# DebugProbe.net
KiCad netlist of a schematic drawn in Altium Designer
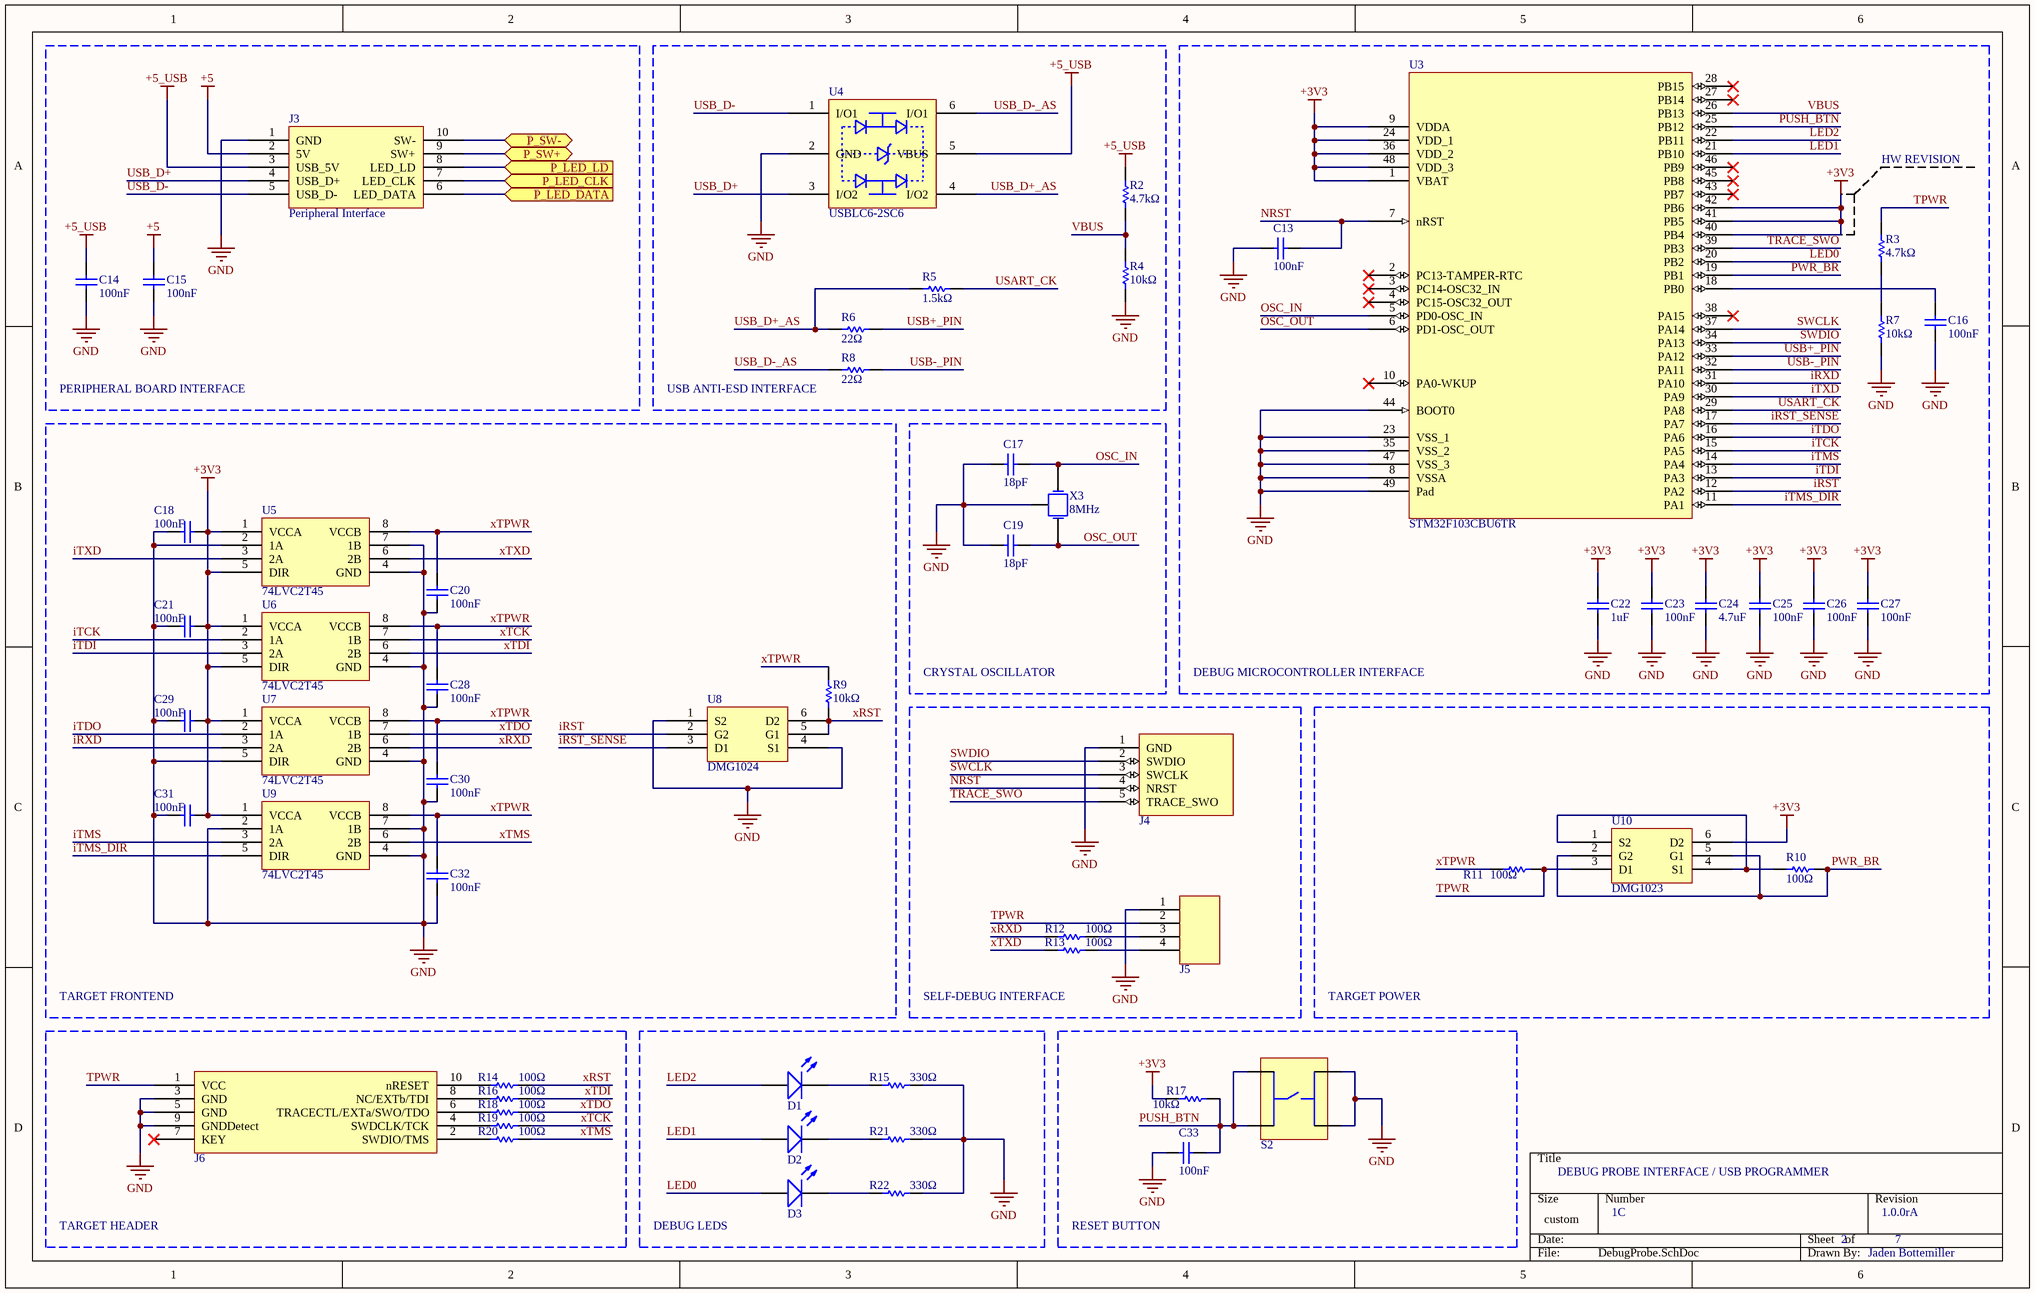
[diagram p0: DebugProbe.SchDoc]

(export (version "E")
  (design (tool "Eeschema 10.0.6"))
  (components
    (comp (ref "C13")
      (value "100nF")
      (description "Standard Capacitor")
      (fields (field (name "Comment") "CAP"))
      (libsource (lib "NikoboticsLib") (part "CAP"))
    )
    (comp (ref "C14")
      (value "100nF")
      (description "Standard Capacitor")
      (fields (field (name "Comment") "CAP"))
      (libsource (lib "NikoboticsLib") (part "CAP"))
    )
    (comp (ref "C15")
      (value "100nF")
      (description "Standard Capacitor")
      (fields (field (name "Comment") "CAP"))
      (libsource (lib "NikoboticsLib") (part "CAP"))
    )
    (comp (ref "C16")
      (value "100nF")
      (description "Standard Capacitor")
      (fields (field (name "Comment") "CAP"))
      (libsource (lib "NikoboticsLib") (part "CAP"))
    )
    (comp (ref "C17")
      (value "18pF")
      (description "Standard Capacitor")
      (fields (field (name "Comment") "CAP"))
      (libsource (lib "NikoboticsLib") (part "CAP"))
    )
    (comp (ref "C18")
      (value "100nF")
      (description "Standard Capacitor")
      (fields (field (name "Comment") "CAP"))
      (libsource (lib "NikoboticsLib") (part "CAP"))
    )
    (comp (ref "C19")
      (value "18pF")
      (description "Standard Capacitor")
      (fields (field (name "Comment") "CAP"))
      (libsource (lib "NikoboticsLib") (part "CAP"))
    )
    (comp (ref "C20")
      (value "100nF")
      (description "Standard Capacitor")
      (fields (field (name "Comment") "CAP"))
      (libsource (lib "NikoboticsLib") (part "CAP"))
    )
    (comp (ref "C21")
      (value "100nF")
      (description "Standard Capacitor")
      (fields (field (name "Comment") "CAP"))
      (libsource (lib "NikoboticsLib") (part "CAP"))
    )
    (comp (ref "C22")
      (value "1uF")
      (description "Standard Capacitor")
      (fields (field (name "Comment") "CAP"))
      (libsource (lib "NikoboticsLib") (part "CAP"))
    )
    (comp (ref "C23")
      (value "100nF")
      (description "Standard Capacitor")
      (fields (field (name "Comment") "CAP"))
      (libsource (lib "NikoboticsLib") (part "CAP"))
    )
    (comp (ref "C24")
      (value "4.7uF")
      (description "Standard Capacitor")
      (fields (field (name "Comment") "CAP"))
      (libsource (lib "NikoboticsLib") (part "CAP"))
    )
    (comp (ref "C25")
      (value "100nF")
      (description "Standard Capacitor")
      (fields (field (name "Comment") "CAP"))
      (libsource (lib "NikoboticsLib") (part "CAP"))
    )
    (comp (ref "C26")
      (value "100nF")
      (description "Standard Capacitor")
      (fields (field (name "Comment") "CAP"))
      (libsource (lib "NikoboticsLib") (part "CAP"))
    )
    (comp (ref "C27")
      (value "100nF")
      (description "Standard Capacitor")
      (fields (field (name "Comment") "CAP"))
      (libsource (lib "NikoboticsLib") (part "CAP"))
    )
    (comp (ref "C28")
      (value "100nF")
      (description "Standard Capacitor")
      (fields (field (name "Comment") "CAP"))
      (libsource (lib "NikoboticsLib") (part "CAP"))
    )
    (comp (ref "C29")
      (value "100nF")
      (description "Standard Capacitor")
      (fields (field (name "Comment") "CAP"))
      (libsource (lib "NikoboticsLib") (part "CAP"))
    )
    (comp (ref "C30")
      (value "100nF")
      (description "Standard Capacitor")
      (fields (field (name "Comment") "CAP"))
      (libsource (lib "NikoboticsLib") (part "CAP"))
    )
    (comp (ref "C31")
      (value "100nF")
      (description "Standard Capacitor")
      (fields (field (name "Comment") "CAP"))
      (libsource (lib "NikoboticsLib") (part "CAP"))
    )
    (comp (ref "C32")
      (value "100nF")
      (description "Standard Capacitor")
      (fields (field (name "Comment") "CAP"))
      (libsource (lib "NikoboticsLib") (part "CAP"))
    )
    (comp (ref "C33")
      (value "100nF")
      (description "Standard Capacitor")
      (fields (field (name "Comment") "CAP"))
      (libsource (lib "NikoboticsLib") (part "CAP"))
    )
    (comp (ref "D1")
      (value "LED")
      (description "Standard LED")
      (libsource (lib "NikoboticsLib") (part "LED"))
    )
    (comp (ref "D2")
      (value "LED")
      (description "Standard LED")
      (libsource (lib "NikoboticsLib") (part "LED"))
    )
    (comp (ref "D3")
      (value "LED")
      (description "Standard LED")
      (libsource (lib "NikoboticsLib") (part "LED"))
    )
    (comp (ref "J3")
      (value "Peripheral Interface")
      (description "Interface between peripheral board and control board.")
      (libsource (lib "NikoboticsLib") (part "PERIPHERAL_INTERFACE"))
    )
    (comp (ref "J4")
      (value "Debug Header")
      (description "Five pin Debug Header SWD")
      (libsource (lib "NikoboticsLib") (part "DBG_5PIN"))
    )
    (comp (ref "J5")
      (value "4 Pin Connector")
      (description "Standard 4 Pin Connector")
      (libsource (lib "NikoboticsLib") (part "CONN_4PIN"))
    )
    (comp (ref "J6")
      (value "Debug Connector")
      (description "10-Pin Cortex-M Debug Connector")
      (libsource (lib "NikoboticsLib") (part "Cortex-M Debug"))
    )
    (comp (ref "R2")
      (value "4.7kΩ")
      (description "Standard Resistor")
      (fields (field (name "Comment") "RES"))
      (libsource (lib "NikoboticsLib") (part "RES"))
    )
    (comp (ref "R3")
      (value "4.7kΩ")
      (description "Standard Resistor")
      (fields (field (name "Comment") "RES"))
      (libsource (lib "NikoboticsLib") (part "RES"))
    )
    (comp (ref "R4")
      (value "10kΩ")
      (description "Standard Resistor")
      (fields (field (name "Comment") "RES"))
      (libsource (lib "NikoboticsLib") (part "RES"))
    )
    (comp (ref "R5")
      (value "1.5kΩ")
      (description "Standard Resistor")
      (fields (field (name "Comment") "RES"))
      (libsource (lib "NikoboticsLib") (part "RES"))
    )
    (comp (ref "R6")
      (value "22Ω")
      (description "Standard Resistor")
      (fields (field (name "Comment") "RES"))
      (libsource (lib "NikoboticsLib") (part "RES"))
    )
    (comp (ref "R7")
      (value "10kΩ")
      (description "Standard Resistor")
      (fields (field (name "Comment") "RES"))
      (libsource (lib "NikoboticsLib") (part "RES"))
    )
    (comp (ref "R8")
      (value "22Ω")
      (description "Standard Resistor")
      (fields (field (name "Comment") "RES"))
      (libsource (lib "NikoboticsLib") (part "RES"))
    )
    (comp (ref "R9")
      (value "10kΩ")
      (description "Standard Resistor")
      (fields (field (name "Comment") "RES"))
      (libsource (lib "NikoboticsLib") (part "RES"))
    )
    (comp (ref "R10")
      (value "100Ω")
      (description "Standard Resistor")
      (fields (field (name "Comment") "RES"))
      (libsource (lib "NikoboticsLib") (part "RES"))
    )
    (comp (ref "R11")
      (value "100Ω")
      (description "Standard Resistor")
      (fields (field (name "Comment") "RES"))
      (libsource (lib "NikoboticsLib") (part "RES"))
    )
    (comp (ref "R12")
      (value "100Ω")
      (description "Standard Resistor")
      (fields (field (name "Comment") "RES"))
      (libsource (lib "NikoboticsLib") (part "RES"))
    )
    (comp (ref "R13")
      (value "100Ω")
      (description "Standard Resistor")
      (fields (field (name "Comment") "RES"))
      (libsource (lib "NikoboticsLib") (part "RES"))
    )
    (comp (ref "R14")
      (value "100Ω")
      (description "Standard Resistor")
      (fields (field (name "Comment") "RES"))
      (libsource (lib "NikoboticsLib") (part "RES"))
    )
    (comp (ref "R15")
      (value "330Ω")
      (description "Standard Resistor")
      (fields (field (name "Comment") "RES"))
      (libsource (lib "NikoboticsLib") (part "RES"))
    )
    (comp (ref "R16")
      (value "100Ω")
      (description "Standard Resistor")
      (fields (field (name "Comment") "RES"))
      (libsource (lib "NikoboticsLib") (part "RES"))
    )
    (comp (ref "R17")
      (value "10kΩ")
      (description "Standard Resistor")
      (fields (field (name "Comment") "RES"))
      (libsource (lib "NikoboticsLib") (part "RES"))
    )
    (comp (ref "R18")
      (value "100Ω")
      (description "Standard Resistor")
      (fields (field (name "Comment") "RES"))
      (libsource (lib "NikoboticsLib") (part "RES"))
    )
    (comp (ref "R19")
      (value "100Ω")
      (description "Standard Resistor")
      (fields (field (name "Comment") "RES"))
      (libsource (lib "NikoboticsLib") (part "RES"))
    )
    (comp (ref "R20")
      (value "100Ω")
      (description "Standard Resistor")
      (fields (field (name "Comment") "RES"))
      (libsource (lib "NikoboticsLib") (part "RES"))
    )
    (comp (ref "R21")
      (value "330Ω")
      (description "Standard Resistor")
      (fields (field (name "Comment") "RES"))
      (libsource (lib "NikoboticsLib") (part "RES"))
    )
    (comp (ref "R22")
      (value "330Ω")
      (description "Standard Resistor")
      (fields (field (name "Comment") "RES"))
      (libsource (lib "NikoboticsLib") (part "RES"))
    )
    (comp (ref "S2")
      (value "Pushbutton")
      (description "Standard Pushbutton with 4 Terminals")
      (libsource (lib "NikoboticsLib") (part "PUSHBTN_4T"))
    )
    (comp (ref "U3")
      (value "STM32F103CBU6TR")
      (description "IC MCU 32BIT 128KB FLASH LQFP48")
      (libsource (lib "NikoboticsLib") (part "STM32F103CBU6TR"))
    )
    (comp (ref "U4")
      (value "USBLC6-2SC6")
      (description "17V Clamp 5A (8/20µs) Ipp TVS Diode")
      (libsource (lib "NikoboticsLib") (part "USBLC6-2"))
    )
    (comp (ref "U5")
      (value "74LVC2T45")
      (description "Voltage Level Translator Bidirectional 1 Circuit 2 Channel 420Mbps 8-XSON")
      (libsource (lib "NikoboticsLib") (part "74LVC2T45"))
    )
    (comp (ref "U6")
      (value "74LVC2T45")
      (description "Voltage Level Translator Bidirectional 1 Circuit 2 Channel 420Mbps 8-XSON")
      (libsource (lib "NikoboticsLib") (part "74LVC2T45"))
    )
    (comp (ref "U7")
      (value "74LVC2T45")
      (description "Voltage Level Translator Bidirectional 1 Circuit 2 Channel 420Mbps 8-XSON")
      (libsource (lib "NikoboticsLib") (part "74LVC2T45"))
    )
    (comp (ref "U8")
      (value "DMG1024")
      (description "Mosfet Array 2 N-Channel (Dual) 20V 1.38A 530mW Surface Mount SOT-563")
      (libsource (lib "NikoboticsLib") (part "DMG1024"))
    )
    (comp (ref "U9")
      (value "74LVC2T45")
      (description "Voltage Level Translator Bidirectional 1 Circuit 2 Channel 420Mbps 8-XSON")
      (libsource (lib "NikoboticsLib") (part "74LVC2T45"))
    )
    (comp (ref "U10")
      (value "DMG1023")
      (description "Mosfet Array 2 P-Channel (Dual) 20V 1.03A 530mW Surface Mount SOT-563")
      (libsource (lib "NikoboticsLib") (part "DMG1023"))
    )
    (comp (ref "X3")
      (value "8MHz")
      (description "Standard Crystal Oscillator with a ground connection.")
      (fields (field (name "Comment") "Crystal Oscillator"))
      (libsource (lib "NikoboticsLib") (part "OSC_1GND"))
    )
  )
  (nets
    (net (code "1") (name "+3V3") (class "Default")
      (node (ref "C18") (pin "1") (pinfunction "1_1") (pintype "passive"))
      (node (ref "C21") (pin "1") (pinfunction "1_1") (pintype "passive"))
      (node (ref "C22") (pin "2") (pinfunction "2_2") (pintype "passive"))
      (node (ref "C23") (pin "2") (pinfunction "2_2") (pintype "passive"))
      (node (ref "C24") (pin "2") (pinfunction "2_2") (pintype "passive"))
      (node (ref "C25") (pin "2") (pinfunction "2_2") (pintype "passive"))
      (node (ref "C26") (pin "2") (pinfunction "2_2") (pintype "passive"))
      (node (ref "C27") (pin "2") (pinfunction "2_2") (pintype "passive"))
      (node (ref "C29") (pin "1") (pinfunction "1_1") (pintype "passive"))
      (node (ref "C31") (pin "1") (pinfunction "1_1") (pintype "passive"))
      (node (ref "R17") (pin "1") (pinfunction "1_1") (pintype "passive"))
      (node (ref "U10") (pin "6") (pinfunction "D2_6") (pintype "passive"))
      (node (ref "U3") (pin "1") (pinfunction "VBAT_1") (pintype "power_in"))
      (node (ref "U3") (pin "24") (pinfunction "VDD_1_24") (pintype "power_in"))
      (node (ref "U3") (pin "36") (pinfunction "VDD_2_36") (pintype "power_in"))
      (node (ref "U3") (pin "40") (pinfunction "PB4_40") (pintype "bidirectional"))
      (node (ref "U3") (pin "41") (pinfunction "PB5_41") (pintype "bidirectional"))
      (node (ref "U3") (pin "42") (pinfunction "PB6_42") (pintype "bidirectional"))
      (node (ref "U3") (pin "48") (pinfunction "VDD_3_48") (pintype "power_in"))
      (node (ref "U3") (pin "9") (pinfunction "VDDA_9") (pintype "power_in"))
      (node (ref "U5") (pin "1") (pinfunction "VCCA_1") (pintype "passive"))
      (node (ref "U5") (pin "5") (pinfunction "DIR_5") (pintype "passive"))
      (node (ref "U6") (pin "1") (pinfunction "VCCA_1") (pintype "passive"))
      (node (ref "U6") (pin "5") (pinfunction "DIR_5") (pintype "passive"))
      (node (ref "U7") (pin "1") (pinfunction "VCCA_1") (pintype "passive"))
      (node (ref "U9") (pin "1") (pinfunction "VCCA_1") (pintype "passive"))
    )
    (net (code "2") (name "+5") (class "Default")
      (node (ref "C15") (pin "2") (pinfunction "2_2") (pintype "passive"))
      (node (ref "J3") (pin "2") (pinfunction "5V_2") (pintype "passive"))
    )
    (net (code "3") (name "+5_USB") (class "Default")
      (node (ref "C14") (pin "2") (pinfunction "2_2") (pintype "passive"))
      (node (ref "J3") (pin "3") (pinfunction "USB_5V_3") (pintype "passive"))
      (node (ref "R2") (pin "2") (pinfunction "2_2") (pintype "passive"))
      (node (ref "U4") (pin "5") (pinfunction "VBUS_5") (pintype "passive"))
    )
    (net (code "4") (name "/LED0") (class "Default")
      (node (ref "D3") (pin "2") (pinfunction "A_2") (pintype "passive"))
      (node (ref "U3") (pin "20") (pinfunction "PB2_20") (pintype "bidirectional"))
    )
    (net (code "5") (name "/LED1") (class "Default")
      (node (ref "D2") (pin "2") (pinfunction "A_2") (pintype "passive"))
      (node (ref "U3") (pin "21") (pinfunction "PB10_21") (pintype "bidirectional"))
    )
    (net (code "6") (name "/LED2") (class "Default")
      (node (ref "D1") (pin "2") (pinfunction "A_2") (pintype "passive"))
      (node (ref "U3") (pin "22") (pinfunction "PB11_22") (pintype "bidirectional"))
    )
    (net (code "7") (name "/NRST") (class "Default")
      (node (ref "C13") (pin "2") (pinfunction "2_2") (pintype "passive"))
      (node (ref "J4") (pin "4") (pinfunction "NRST_4") (pintype "bidirectional"))
      (node (ref "U3") (pin "7") (pinfunction "nRST_7") (pintype "input"))
    )
    (net (code "8") (name "/OSC_IN") (class "Default")
      (node (ref "C17") (pin "1") (pinfunction "1_1") (pintype "passive"))
      (node (ref "U3") (pin "5") (pinfunction "PD0-OSC_IN_5") (pintype "bidirectional"))
      (node (ref "X3") (pin "1") (pinfunction "X1_1") (pintype "passive"))
    )
    (net (code "9") (name "/OSC_OUT") (class "Default")
      (node (ref "C19") (pin "1") (pinfunction "1_1") (pintype "passive"))
      (node (ref "U3") (pin "6") (pinfunction "PD1-OSC_OUT_6") (pintype "bidirectional"))
      (node (ref "X3") (pin "2") (pinfunction "X2_2") (pintype "passive"))
    )
    (net (code "10") (name "/PUSH_BTN") (class "Default")
      (node (ref "C33") (pin "1") (pinfunction "1_1") (pintype "passive"))
      (node (ref "R17") (pin "2") (pinfunction "2_2") (pintype "passive"))
      (node (ref "S2") (pin "1") (pintype "passive"))
      (node (ref "S2") (pin "2") (pinfunction "Pin_2") (pintype "passive"))
      (node (ref "U3") (pin "25") (pinfunction "PB12_25") (pintype "bidirectional"))
    )
    (net (code "11") (name "/PWR_BR") (class "Default")
      (node (ref "R10") (pin "2") (pinfunction "2_2") (pintype "passive"))
      (node (ref "U10") (pin "2") (pinfunction "G2_2") (pintype "passive"))
      (node (ref "U10") (pin "5") (pinfunction "G1_5") (pintype "passive"))
      (node (ref "U3") (pin "19") (pinfunction "PB1_19") (pintype "bidirectional"))
    )
    (net (code "12") (name "/P_LED_CLK") (class "Default")
      (node (ref "J3") (pin "7") (pinfunction "LED_CLK_7") (pintype "passive"))
    )
    (net (code "13") (name "/P_LED_DATA") (class "Default")
      (node (ref "J3") (pin "6") (pinfunction "LED_DATA_6") (pintype "passive"))
    )
    (net (code "14") (name "/P_LED_LD") (class "Default")
      (node (ref "J3") (pin "8") (pinfunction "LED_LD_8") (pintype "passive"))
    )
    (net (code "15") (name "/P_SW+") (class "Default")
      (node (ref "J3") (pin "9") (pinfunction "SW+_9") (pintype "passive"))
    )
    (net (code "16") (name "/P_SW-") (class "Default")
      (node (ref "J3") (pin "10") (pinfunction "SW-_10") (pintype "passive"))
    )
    (net (code "17") (name "/SWCLK") (class "Default")
      (node (ref "J4") (pin "3") (pinfunction "SWCLK_3") (pintype "bidirectional"))
      (node (ref "U3") (pin "37") (pinfunction "PA14_37") (pintype "bidirectional"))
    )
    (net (code "18") (name "/SWDIO") (class "Default")
      (node (ref "J4") (pin "2") (pinfunction "SWDIO_2") (pintype "bidirectional"))
      (node (ref "U3") (pin "34") (pinfunction "PA13_34") (pintype "bidirectional"))
    )
    (net (code "19") (name "/TPWR") (class "Default")
      (node (ref "J5") (pin "2") (pinfunction "Pin_2") (pintype "passive"))
      (node (ref "J6") (pin "1") (pinfunction "VCC_1") (pintype "power_in"))
      (node (ref "R11") (pin "2") (pinfunction "2_2") (pintype "passive"))
      (node (ref "R3") (pin "2") (pinfunction "2_2") (pintype "passive"))
      (node (ref "U10") (pin "3") (pinfunction "D1_3") (pintype "passive"))
    )
    (net (code "20") (name "/TRACE_SWO") (class "Default")
      (node (ref "J4") (pin "5") (pinfunction "TRACE_SWO_5") (pintype "bidirectional"))
      (node (ref "U3") (pin "39") (pinfunction "PB3_39") (pintype "bidirectional"))
    )
    (net (code "21") (name "/USART_CK") (class "Default")
      (node (ref "R5") (pin "1") (pinfunction "1_1") (pintype "passive"))
      (node (ref "U3") (pin "29") (pinfunction "PA8_29") (pintype "bidirectional"))
    )
    (net (code "22") (name "/USB+_PIN") (class "Default")
      (node (ref "R6") (pin "1") (pinfunction "1_1") (pintype "passive"))
      (node (ref "U3") (pin "33") (pinfunction "PA12_33") (pintype "bidirectional"))
    )
    (net (code "23") (name "/USB-_PIN") (class "Default")
      (node (ref "R8") (pin "1") (pinfunction "1_1") (pintype "passive"))
      (node (ref "U3") (pin "32") (pinfunction "PA11_32") (pintype "bidirectional"))
    )
    (net (code "24") (name "/USB_D+") (class "Default")
      (node (ref "J3") (pin "4") (pinfunction "USB_D+_4") (pintype "passive"))
      (node (ref "U4") (pin "3") (pinfunction "I/O2_3") (pintype "passive"))
    )
    (net (code "25") (name "/USB_D+_AS") (class "Default")
      (node (ref "R5") (pin "2") (pinfunction "2_2") (pintype "passive"))
      (node (ref "R6") (pin "2") (pinfunction "2_2") (pintype "passive"))
      (node (ref "U4") (pin "4") (pinfunction "I/O2_4") (pintype "passive"))
    )
    (net (code "26") (name "/USB_D-") (class "Default")
      (node (ref "J3") (pin "5") (pinfunction "USB_D-_5") (pintype "passive"))
      (node (ref "U4") (pin "1") (pinfunction "I/O1_1") (pintype "passive"))
    )
    (net (code "27") (name "/USB_D-_AS") (class "Default")
      (node (ref "R8") (pin "2") (pinfunction "2_2") (pintype "passive"))
      (node (ref "U4") (pin "6") (pinfunction "I/O1_6") (pintype "passive"))
    )
    (net (code "28") (name "/VBUS") (class "Default")
      (node (ref "R2") (pin "1") (pinfunction "1_1") (pintype "passive"))
      (node (ref "R4") (pin "2") (pinfunction "2_2") (pintype "passive"))
      (node (ref "U3") (pin "26") (pinfunction "PB13_26") (pintype "bidirectional"))
    )
    (net (code "29") (name "/iRST") (class "Default")
      (node (ref "U3") (pin "12") (pinfunction "PA2_12") (pintype "bidirectional"))
      (node (ref "U8") (pin "2") (pinfunction "G2_2") (pintype "passive"))
    )
    (net (code "30") (name "/iRST_SENSE") (class "Default")
      (node (ref "U3") (pin "17") (pinfunction "PA7_17") (pintype "bidirectional"))
      (node (ref "U8") (pin "3") (pinfunction "D1_3") (pintype "passive"))
    )
    (net (code "31") (name "/iRXD") (class "Default")
      (node (ref "U3") (pin "31") (pinfunction "PA10_31") (pintype "bidirectional"))
      (node (ref "U7") (pin "3") (pinfunction "2A_3") (pintype "passive"))
    )
    (net (code "32") (name "/iTCK") (class "Default")
      (node (ref "U3") (pin "15") (pinfunction "PA5_15") (pintype "bidirectional"))
      (node (ref "U6") (pin "2") (pinfunction "1A_2") (pintype "passive"))
    )
    (net (code "33") (name "/iTDI") (class "Default")
      (node (ref "U3") (pin "13") (pinfunction "PA3_13") (pintype "bidirectional"))
      (node (ref "U6") (pin "3") (pinfunction "2A_3") (pintype "passive"))
    )
    (net (code "34") (name "/iTDO") (class "Default")
      (node (ref "U3") (pin "16") (pinfunction "PA6_16") (pintype "bidirectional"))
      (node (ref "U7") (pin "2") (pinfunction "1A_2") (pintype "passive"))
    )
    (net (code "35") (name "/iTMS") (class "Default")
      (node (ref "U3") (pin "14") (pinfunction "PA4_14") (pintype "bidirectional"))
      (node (ref "U9") (pin "3") (pinfunction "2A_3") (pintype "passive"))
    )
    (net (code "36") (name "/iTMS_DIR") (class "Default")
      (node (ref "U3") (pin "11") (pinfunction "PA1_11") (pintype "bidirectional"))
      (node (ref "U9") (pin "5") (pinfunction "DIR_5") (pintype "passive"))
    )
    (net (code "37") (name "/iTXD") (class "Default")
      (node (ref "U3") (pin "30") (pinfunction "PA9_30") (pintype "bidirectional"))
      (node (ref "U5") (pin "3") (pinfunction "2A_3") (pintype "passive"))
    )
    (net (code "38") (name "/xRST") (class "Default")
      (node (ref "R14") (pin "1") (pinfunction "1_1") (pintype "passive"))
      (node (ref "R9") (pin "2") (pinfunction "2_2") (pintype "passive"))
      (node (ref "U8") (pin "5") (pinfunction "G1_5") (pintype "passive"))
      (node (ref "U8") (pin "6") (pinfunction "D2_6") (pintype "passive"))
    )
    (net (code "39") (name "/xRXD") (class "Default")
      (node (ref "R12") (pin "2") (pinfunction "2_2") (pintype "passive"))
      (node (ref "U7") (pin "6") (pinfunction "2B_6") (pintype "passive"))
    )
    (net (code "40") (name "/xTCK") (class "Default")
      (node (ref "R19") (pin "1") (pinfunction "1_1") (pintype "passive"))
      (node (ref "U6") (pin "7") (pinfunction "1B_7") (pintype "passive"))
    )
    (net (code "41") (name "/xTDI") (class "Default")
      (node (ref "R16") (pin "1") (pinfunction "1_1") (pintype "passive"))
      (node (ref "U6") (pin "6") (pinfunction "2B_6") (pintype "passive"))
    )
    (net (code "42") (name "/xTDO") (class "Default")
      (node (ref "R18") (pin "1") (pinfunction "1_1") (pintype "passive"))
      (node (ref "U7") (pin "7") (pinfunction "1B_7") (pintype "passive"))
    )
    (net (code "43") (name "/xTMS") (class "Default")
      (node (ref "R20") (pin "1") (pinfunction "1_1") (pintype "passive"))
      (node (ref "U9") (pin "6") (pinfunction "2B_6") (pintype "passive"))
    )
    (net (code "44") (name "/xTPWR") (class "Default")
      (node (ref "C20") (pin "1") (pinfunction "1_1") (pintype "passive"))
      (node (ref "C28") (pin "1") (pinfunction "1_1") (pintype "passive"))
      (node (ref "C30") (pin "1") (pinfunction "1_1") (pintype "passive"))
      (node (ref "C32") (pin "1") (pinfunction "1_1") (pintype "passive"))
      (node (ref "R11") (pin "1") (pinfunction "1_1") (pintype "passive"))
      (node (ref "R9") (pin "1") (pinfunction "1_1") (pintype "passive"))
      (node (ref "U5") (pin "8") (pinfunction "VCCB_8") (pintype "passive"))
      (node (ref "U6") (pin "8") (pinfunction "VCCB_8") (pintype "passive"))
      (node (ref "U7") (pin "8") (pinfunction "VCCB_8") (pintype "passive"))
      (node (ref "U9") (pin "8") (pinfunction "VCCB_8") (pintype "passive"))
    )
    (net (code "45") (name "/xTXD") (class "Default")
      (node (ref "R13") (pin "2") (pinfunction "2_2") (pintype "passive"))
      (node (ref "U5") (pin "6") (pinfunction "2B_6") (pintype "passive"))
    )
    (net (code "46") (name "GND") (class "Default")
      (node (ref "C13") (pin "1") (pinfunction "1_1") (pintype "passive"))
      (node (ref "C14") (pin "1") (pinfunction "1_1") (pintype "passive"))
      (node (ref "C15") (pin "1") (pinfunction "1_1") (pintype "passive"))
      (node (ref "C16") (pin "1") (pinfunction "1_1") (pintype "passive"))
      (node (ref "C17") (pin "2") (pinfunction "2_2") (pintype "passive"))
      (node (ref "C18") (pin "2") (pinfunction "2_2") (pintype "passive"))
      (node (ref "C19") (pin "2") (pinfunction "2_2") (pintype "passive"))
      (node (ref "C20") (pin "2") (pinfunction "2_2") (pintype "passive"))
      (node (ref "C21") (pin "2") (pinfunction "2_2") (pintype "passive"))
      (node (ref "C22") (pin "1") (pinfunction "1_1") (pintype "passive"))
      (node (ref "C23") (pin "1") (pinfunction "1_1") (pintype "passive"))
      (node (ref "C24") (pin "1") (pinfunction "1_1") (pintype "passive"))
      (node (ref "C25") (pin "1") (pinfunction "1_1") (pintype "passive"))
      (node (ref "C26") (pin "1") (pinfunction "1_1") (pintype "passive"))
      (node (ref "C27") (pin "1") (pinfunction "1_1") (pintype "passive"))
      (node (ref "C28") (pin "2") (pinfunction "2_2") (pintype "passive"))
      (node (ref "C29") (pin "2") (pinfunction "2_2") (pintype "passive"))
      (node (ref "C30") (pin "2") (pinfunction "2_2") (pintype "passive"))
      (node (ref "C31") (pin "2") (pinfunction "2_2") (pintype "passive"))
      (node (ref "C32") (pin "2") (pinfunction "2_2") (pintype "passive"))
      (node (ref "C33") (pin "2") (pinfunction "2_2") (pintype "passive"))
      (node (ref "J3") (pin "1") (pinfunction "GND_1") (pintype "passive"))
      (node (ref "J4") (pin "1") (pinfunction "GND_1") (pintype "power_in"))
      (node (ref "J5") (pin "1") (pinfunction "Pin_1") (pintype "passive"))
      (node (ref "J6") (pin "3") (pinfunction "GND_3") (pintype "power_in"))
      (node (ref "J6") (pin "5") (pinfunction "GND_5") (pintype "power_in"))
      (node (ref "J6") (pin "9") (pinfunction "GNDDetect_9") (pintype "power_in"))
      (node (ref "R15") (pin "1") (pinfunction "1_1") (pintype "passive"))
      (node (ref "R21") (pin "1") (pinfunction "1_1") (pintype "passive"))
      (node (ref "R22") (pin "1") (pinfunction "1_1") (pintype "passive"))
      (node (ref "R4") (pin "1") (pinfunction "1_1") (pintype "passive"))
      (node (ref "R7") (pin "1") (pinfunction "1_1") (pintype "passive"))
      (node (ref "S2") (pin "3") (pinfunction "Pin_3") (pintype "passive"))
      (node (ref "S2") (pin "4") (pinfunction "Pin_4") (pintype "passive"))
      (node (ref "U3") (pin "23") (pinfunction "VSS_1_23") (pintype "power_in"))
      (node (ref "U3") (pin "35") (pinfunction "VSS_2_35") (pintype "power_in"))
      (node (ref "U3") (pin "44") (pinfunction "BOOT0_44") (pintype "input"))
      (node (ref "U3") (pin "47") (pinfunction "VSS_3_47") (pintype "power_in"))
      (node (ref "U3") (pin "49") (pinfunction "Pad_49") (pintype "power_in"))
      (node (ref "U3") (pin "8") (pinfunction "VSSA_8") (pintype "power_in"))
      (node (ref "U4") (pin "2") (pinfunction "GND_2") (pintype "passive"))
      (node (ref "U5") (pin "2") (pinfunction "1A_2") (pintype "passive"))
      (node (ref "U5") (pin "4") (pinfunction "GND_4") (pintype "passive"))
      (node (ref "U5") (pin "7") (pinfunction "1B_7") (pintype "passive"))
      (node (ref "U6") (pin "4") (pinfunction "GND_4") (pintype "passive"))
      (node (ref "U7") (pin "4") (pinfunction "GND_4") (pintype "passive"))
      (node (ref "U7") (pin "5") (pinfunction "DIR_5") (pintype "passive"))
      (node (ref "U8") (pin "1") (pinfunction "S2_1") (pintype "passive"))
      (node (ref "U8") (pin "4") (pinfunction "S1_4") (pintype "passive"))
      (node (ref "U9") (pin "2") (pinfunction "1A_2") (pintype "passive"))
      (node (ref "U9") (pin "4") (pinfunction "GND_4") (pintype "passive"))
      (node (ref "U9") (pin "7") (pinfunction "1B_7") (pintype "passive"))
      (node (ref "X3") (pin "3") (pinfunction "GND_3") (pintype "passive"))
    )
    (net (code "47") (name "Net-(D1-K)") (class "Default")
      (node (ref "D1") (pin "1") (pinfunction "K_1") (pintype "passive"))
      (node (ref "R15") (pin "2") (pinfunction "2_2") (pintype "passive"))
    )
    (net (code "48") (name "Net-(D2-K)") (class "Default")
      (node (ref "D2") (pin "1") (pinfunction "K_1") (pintype "passive"))
      (node (ref "R21") (pin "2") (pinfunction "2_2") (pintype "passive"))
    )
    (net (code "49") (name "Net-(D3-K)") (class "Default")
      (node (ref "D3") (pin "1") (pinfunction "K_1") (pintype "passive"))
      (node (ref "R22") (pin "2") (pinfunction "2_2") (pintype "passive"))
    )
    (net (code "50") (name "Net-(J5-Pin-Pad3)") (class "Default")
      (node (ref "J5") (pin "3") (pinfunction "Pin_3") (pintype "passive"))
      (node (ref "R12") (pin "1") (pinfunction "1_1") (pintype "passive"))
    )
    (net (code "51") (name "Net-(J5-Pin-Pad4)") (class "Default")
      (node (ref "J5") (pin "4") (pinfunction "Pin_4") (pintype "passive"))
      (node (ref "R13") (pin "1") (pinfunction "1_1") (pintype "passive"))
    )
    (net (code "52") (name "Net-(J6-NC{slash}EXTb{slash}TDI)") (class "Default")
      (node (ref "J6") (pin "8") (pinfunction "NC/EXTb/TDI_8") (pintype "passive"))
      (node (ref "R16") (pin "2") (pinfunction "2_2") (pintype "passive"))
    )
    (net (code "53") (name "Net-(J6-SWDCLK{slash}TCK)") (class "Default")
      (node (ref "J6") (pin "4") (pinfunction "SWDCLK/TCK_4") (pintype "passive"))
      (node (ref "R19") (pin "2") (pinfunction "2_2") (pintype "passive"))
    )
    (net (code "54") (name "Net-(J6-SWDIO{slash}TMS)") (class "Default")
      (node (ref "J6") (pin "2") (pinfunction "SWDIO/TMS_2") (pintype "passive"))
      (node (ref "R20") (pin "2") (pinfunction "2_2") (pintype "passive"))
    )
    (net (code "55") (name "Net-(J6-TRACECTL{slash}EXTa{slash}SWO{slash}TDO)") (class "Default")
      (node (ref "J6") (pin "6") (pinfunction "TRACECTL/EXTa/SWO/TDO_6") (pintype "passive"))
      (node (ref "R18") (pin "2") (pinfunction "2_2") (pintype "passive"))
    )
    (net (code "56") (name "Net-(J6-nRESET)") (class "Default")
      (node (ref "J6") (pin "10") (pinfunction "nRESET_10") (pintype "passive"))
      (node (ref "R14") (pin "2") (pinfunction "2_2") (pintype "passive"))
    )
    (net (code "57") (name "Net-(R3-Pad1)") (class "Default")
      (node (ref "R3") (pin "1") (pinfunction "1_1") (pintype "passive"))
      (node (ref "R7") (pin "2") (pinfunction "2_2") (pintype "passive"))
    )
    (net (code "58") (name "Net-(U3-PB0)") (class "Default")
      (node (ref "C16") (pin "2") (pinfunction "2_2") (pintype "passive"))
      (node (ref "U3") (pin "18") (pinfunction "PB0_18") (pintype "bidirectional"))
    )
    (net (code "59") (name "Net-(U10-S1)") (class "Default")
      (node (ref "R10") (pin "1") (pinfunction "1_1") (pintype "passive"))
      (node (ref "U10") (pin "1") (pinfunction "S2_1") (pintype "passive"))
      (node (ref "U10") (pin "4") (pinfunction "S1_4") (pintype "passive"))
    )
    (net (code "60") (name "unconnected-(J6-KEY-Pad7)") (class "Default")
      (node (ref "J6") (pin "7") (pinfunction "KEY_7") (pintype "passive+no_connect"))
    )
    (net (code "61") (name "unconnected-(U3-PA0-WKUP-Pad10)") (class "Default")
      (node (ref "U3") (pin "10") (pinfunction "PA0-WKUP_10") (pintype "bidirectional+no_connect"))
    )
    (net (code "62") (name "unconnected-(U3-PA15-Pad38)") (class "Default")
      (node (ref "U3") (pin "38") (pinfunction "PA15_38") (pintype "bidirectional+no_connect"))
    )
    (net (code "63") (name "unconnected-(U3-PB7-Pad43)") (class "Default")
      (node (ref "U3") (pin "43") (pinfunction "PB7_43") (pintype "bidirectional+no_connect"))
    )
    (net (code "64") (name "unconnected-(U3-PB8-Pad45)") (class "Default")
      (node (ref "U3") (pin "45") (pinfunction "PB8_45") (pintype "bidirectional+no_connect"))
    )
    (net (code "65") (name "unconnected-(U3-PB9-Pad46)") (class "Default")
      (node (ref "U3") (pin "46") (pinfunction "PB9_46") (pintype "bidirectional+no_connect"))
    )
    (net (code "66") (name "unconnected-(U3-PB14-Pad27)") (class "Default")
      (node (ref "U3") (pin "27") (pinfunction "PB14_27") (pintype "bidirectional+no_connect"))
    )
    (net (code "67") (name "unconnected-(U3-PB15-Pad28)") (class "Default")
      (node (ref "U3") (pin "28") (pinfunction "PB15_28") (pintype "bidirectional+no_connect"))
    )
    (net (code "68") (name "unconnected-(U3-PC13-TAMPER-RTC-Pad2)") (class "Default")
      (node (ref "U3") (pin "2") (pinfunction "PC13-TAMPER-RTC_2") (pintype "bidirectional+no_connect"))
    )
    (net (code "69") (name "unconnected-(U3-PC14-OSC32_IN-Pad3)") (class "Default")
      (node (ref "U3") (pin "3") (pinfunction "PC14-OSC32_IN_3") (pintype "bidirectional+no_connect"))
    )
    (net (code "70") (name "unconnected-(U3-PC15-OSC32_OUT-Pad4)") (class "Default")
      (node (ref "U3") (pin "4") (pinfunction "PC15-OSC32_OUT_4") (pintype "bidirectional+no_connect"))
    )
  )
)
